# sdram_sram.net
KiCad netlist of a schematic drawn in Altium Designer
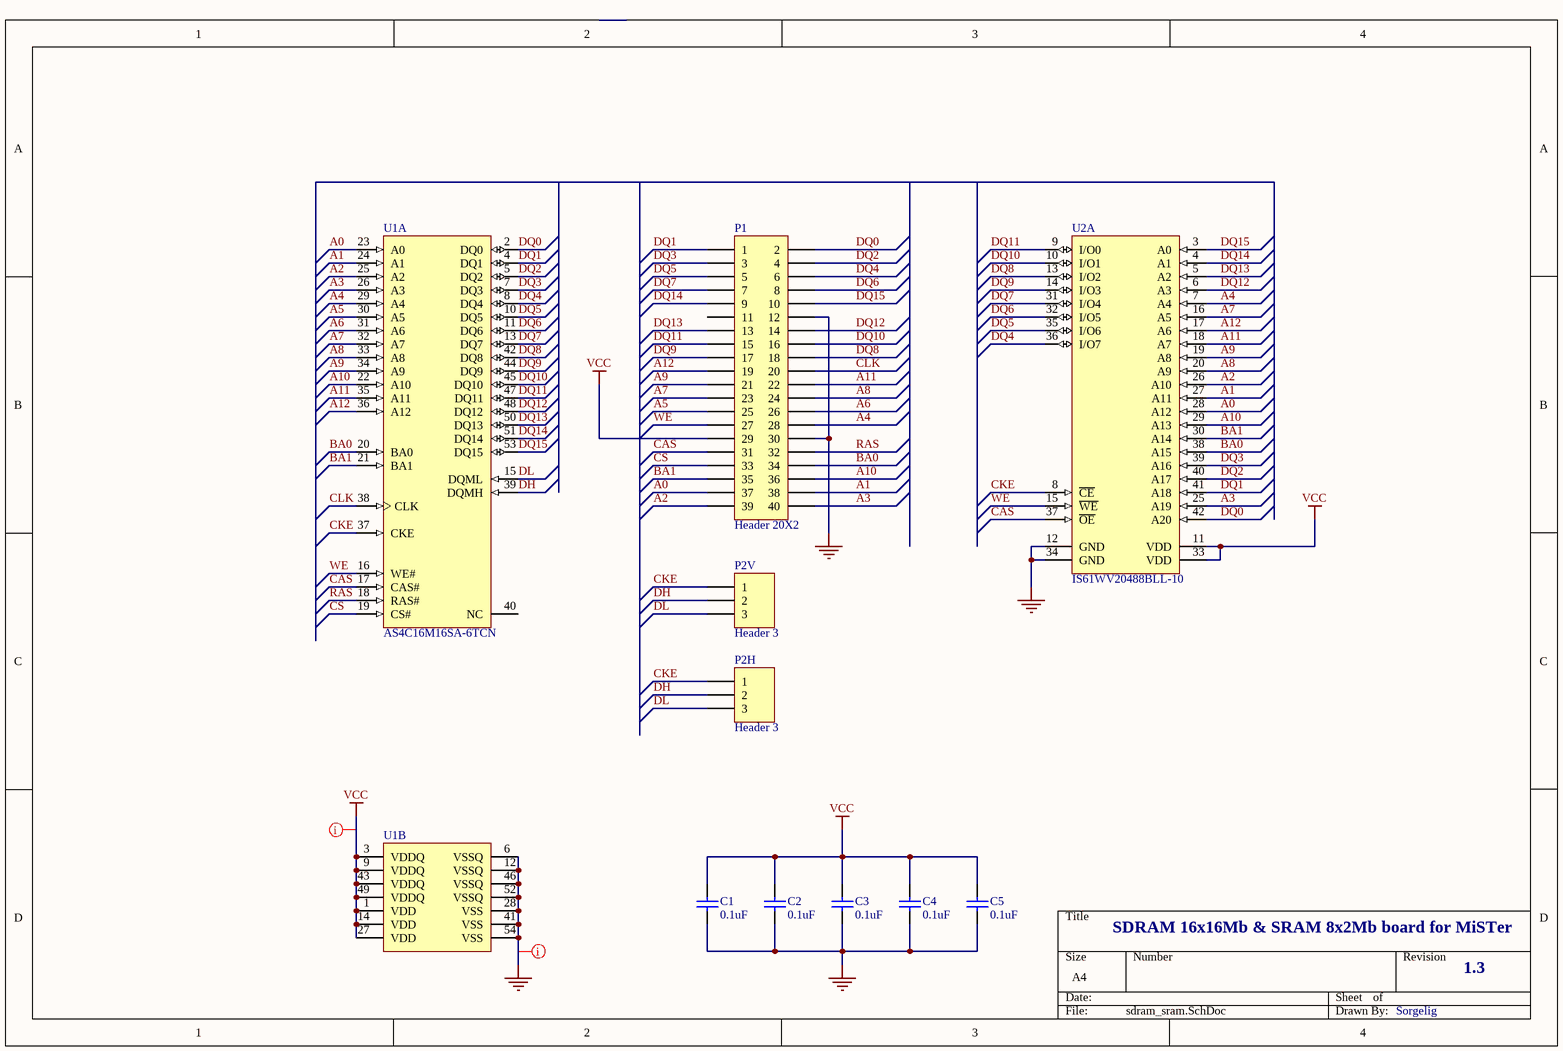
[diagram p0: sdram_sram.SchDoc]

(export (version "E")
  (design (tool "Eeschema 10.0.6"))
  (components
    (comp (ref "C1")
      (value "0.1uF")
      (footprint "C0805")
      (description "Ceramic Chip Capacitor - Standard")
      (fields (field (name "Comment") "C0805") (field (name "PUBLISHER") "Altium Limited"))
      (libsource (lib "lib") (part "C0805"))
    )
    (comp (ref "C2")
      (value "0.1uF")
      (footprint "C0805")
      (description "Ceramic Chip Capacitor - Standard")
      (fields (field (name "Comment") "C0805") (field (name "PUBLISHER") "Altium Limited"))
      (libsource (lib "lib") (part "C0805"))
    )
    (comp (ref "C3")
      (value "0.1uF")
      (footprint "C0805")
      (description "Ceramic Chip Capacitor - Standard")
      (fields (field (name "Comment") "+") (field (name "PUBLISHER") "Altium Limited"))
      (libsource (lib "lib") (part "C0805"))
    )
    (comp (ref "C4")
      (value "0.1uF")
      (footprint "C0805")
      (description "Ceramic Chip Capacitor - Standard")
      (fields (field (name "Comment") "C0805") (field (name "PUBLISHER") "Altium Limited"))
      (libsource (lib "lib") (part "C0805"))
    )
    (comp (ref "C5")
      (value "0.1uF")
      (footprint "C0805")
      (description "Ceramic Chip Capacitor - Standard")
      (fields (field (name "Comment") "+") (field (name "PUBLISHER") "Altium Limited"))
      (libsource (lib "lib") (part "C0805"))
    )
    (comp (ref "P1")
      (value "Header 20X2")
      (footprint "HDR20x2_90")
      (description "Header, 20-Pin, Dual row")
      (fields (field (name "PUBLISHER") "Altium Limited"))
      (libsource (lib "Miscellaneous Connectors") (part "Header 20X2"))
    )
    (comp (ref "P2H")
      (value "Header 3")
      (footprint "HDR1X3")
      (description "Header, 3-Pin")
      (fields (field (name "PUBLISHER") "Altium Limited"))
      (libsource (lib "Miscellaneous Connectors") (part "Header 3"))
    )
    (comp (ref "P2V")
      (value "Header 3")
      (footprint "HDR1X3")
      (description "Header, 3-Pin")
      (fields (field (name "PUBLISHER") "Altium Limited"))
      (libsource (lib "Miscellaneous Connectors") (part "Header 3"))
    )
    (comp (ref "U1")
      (value "AS4C16M16SA-6TCN")
      (footprint "TSOP54")
      (description "256Mb SDR SDRAM, 16Mb x 16, 6ns, 3.3V, 54-Pin TSOP")
      (fields (field (name "VOLTAGE") "3.3V ") (field (name "MANUFACTURER") "Micron"))
      (libsource (lib "lib") (part "AS4C16M16SA-6TCN"))
    )
    (comp (ref "U2")
      (value "IS61WV20488BLL-10")
      (footprint "ISSI-TSOP-2-44_N")
      (description "16 M High Speed CMOS SRAM, 2 M x 8, -40 to 85 degC, 44-Pin SOP (TSOP-2-44)")
      (fields
        (field (name "MANUFACTURER") "Integrated Silicon Solution Inc (ISSI)")
        (field (name "PARTNUMBER") "IS61WV20488BLL-10TI")
      )
      (libsource (lib "ISSI SRAM Asynchronous SRAM High Speed Low Power") (part "IS61WV20488BLL-10TI"))
    )
  )
  (nets
    (net (code "1") (name "/A0") (class "Default")
      (node (ref "P1") (pin "37") (pinfunction "37_37") (pintype "passive"))
      (node (ref "U1") (pin "23") (pinfunction "A0_23") (pintype "input"))
      (node (ref "U2") (pin "28") (pinfunction "A12_28") (pintype "input"))
    )
    (net (code "2") (name "/A1") (class "Default")
      (node (ref "P1") (pin "38") (pinfunction "38_38") (pintype "passive"))
      (node (ref "U1") (pin "24") (pinfunction "A1_24") (pintype "input"))
      (node (ref "U2") (pin "27") (pinfunction "A11_27") (pintype "input"))
    )
    (net (code "3") (name "/A2") (class "Default")
      (node (ref "P1") (pin "39") (pinfunction "39_39") (pintype "passive"))
      (node (ref "U1") (pin "25") (pinfunction "A2_25") (pintype "input"))
      (node (ref "U2") (pin "26") (pinfunction "A10_26") (pintype "input"))
    )
    (net (code "4") (name "/A3") (class "Default")
      (node (ref "P1") (pin "40") (pinfunction "40_40") (pintype "passive"))
      (node (ref "U1") (pin "26") (pinfunction "A3_26") (pintype "input"))
      (node (ref "U2") (pin "25") (pinfunction "A19_25") (pintype "input"))
    )
    (net (code "5") (name "/A4") (class "Default")
      (node (ref "P1") (pin "28") (pinfunction "28_28") (pintype "passive"))
      (node (ref "U1") (pin "29") (pinfunction "A4_29") (pintype "input"))
      (node (ref "U2") (pin "7") (pinfunction "A4_7") (pintype "input"))
    )
    (net (code "6") (name "/A5") (class "Default")
      (node (ref "P1") (pin "25") (pinfunction "25_25") (pintype "passive"))
      (node (ref "U1") (pin "30") (pinfunction "A5_30") (pintype "input"))
    )
    (net (code "7") (name "/A6") (class "Default")
      (node (ref "P1") (pin "26") (pinfunction "26_26") (pintype "passive"))
      (node (ref "U1") (pin "31") (pinfunction "A6_31") (pintype "input"))
    )
    (net (code "8") (name "/A7") (class "Default")
      (node (ref "P1") (pin "23") (pinfunction "23_23") (pintype "passive"))
      (node (ref "U1") (pin "32") (pinfunction "A7_32") (pintype "input"))
      (node (ref "U2") (pin "16") (pinfunction "A5_16") (pintype "input"))
    )
    (net (code "9") (name "/A8") (class "Default")
      (node (ref "P1") (pin "24") (pinfunction "24_24") (pintype "passive"))
      (node (ref "U1") (pin "33") (pinfunction "A8_33") (pintype "input"))
      (node (ref "U2") (pin "20") (pinfunction "A9_20") (pintype "input"))
    )
    (net (code "10") (name "/A9") (class "Default")
      (node (ref "P1") (pin "21") (pinfunction "21_21") (pintype "passive"))
      (node (ref "U1") (pin "34") (pinfunction "A9_34") (pintype "input"))
      (node (ref "U2") (pin "19") (pinfunction "A8_19") (pintype "input"))
    )
    (net (code "11") (name "/A10") (class "Default")
      (node (ref "P1") (pin "36") (pinfunction "36_36") (pintype "passive"))
      (node (ref "U1") (pin "22") (pinfunction "A10_22") (pintype "input"))
      (node (ref "U2") (pin "29") (pinfunction "A13_29") (pintype "input"))
    )
    (net (code "12") (name "/A11") (class "Default")
      (node (ref "P1") (pin "22") (pinfunction "22_22") (pintype "passive"))
      (node (ref "U1") (pin "35") (pinfunction "A11_35") (pintype "input"))
      (node (ref "U2") (pin "18") (pinfunction "A7_18") (pintype "input"))
    )
    (net (code "13") (name "/A12") (class "Default")
      (node (ref "P1") (pin "19") (pinfunction "19_19") (pintype "passive"))
      (node (ref "U1") (pin "36") (pinfunction "A12_36") (pintype "input"))
      (node (ref "U2") (pin "17") (pinfunction "A6_17") (pintype "input"))
    )
    (net (code "14") (name "/BA0") (class "Default")
      (node (ref "P1") (pin "34") (pinfunction "34_34") (pintype "passive"))
      (node (ref "U1") (pin "20") (pinfunction "BA0_20") (pintype "input"))
      (node (ref "U2") (pin "38") (pinfunction "A15_38") (pintype "input"))
    )
    (net (code "15") (name "/BA1") (class "Default")
      (node (ref "P1") (pin "35") (pinfunction "35_35") (pintype "passive"))
      (node (ref "U1") (pin "21") (pinfunction "BA1_21") (pintype "input"))
      (node (ref "U2") (pin "30") (pinfunction "A14_30") (pintype "input"))
    )
    (net (code "16") (name "/CAS") (class "Default")
      (node (ref "P1") (pin "31") (pinfunction "31_31") (pintype "passive"))
      (node (ref "U1") (pin "17") (pinfunction "CAS#_17") (pintype "input"))
      (node (ref "U2") (pin "37") (pinfunction "~{OE}_37") (pintype "input"))
    )
    (net (code "17") (name "/CKE") (class "Default")
      (node (ref "P2H") (pin "1") (pinfunction "1_1") (pintype "passive"))
      (node (ref "P2V") (pin "1") (pinfunction "1_1") (pintype "passive"))
      (node (ref "U1") (pin "37") (pinfunction "CKE_37") (pintype "input"))
      (node (ref "U2") (pin "8") (pinfunction "~{CE}_8") (pintype "input"))
    )
    (net (code "18") (name "/CLK") (class "Default")
      (node (ref "P1") (pin "20") (pinfunction "20_20") (pintype "passive"))
      (node (ref "U1") (pin "38") (pinfunction "CLK_38") (pintype "input"))
    )
    (net (code "19") (name "/CS") (class "Default")
      (node (ref "P1") (pin "33") (pinfunction "33_33") (pintype "passive"))
      (node (ref "U1") (pin "19") (pinfunction "CS#_19") (pintype "input"))
    )
    (net (code "20") (name "/DH") (class "Default")
      (node (ref "P2H") (pin "2") (pinfunction "2_2") (pintype "passive"))
      (node (ref "P2V") (pin "2") (pinfunction "2_2") (pintype "passive"))
      (node (ref "U1") (pin "39") (pinfunction "DQMH_39") (pintype "input"))
    )
    (net (code "21") (name "/DL") (class "Default")
      (node (ref "P2H") (pin "3") (pinfunction "3_3") (pintype "passive"))
      (node (ref "P2V") (pin "3") (pinfunction "3_3") (pintype "passive"))
      (node (ref "U1") (pin "15") (pinfunction "DQML_15") (pintype "input"))
    )
    (net (code "22") (name "/DQ0") (class "Default")
      (node (ref "P1") (pin "2") (pinfunction "2_2") (pintype "passive"))
      (node (ref "U1") (pin "2") (pinfunction "DQ0_2") (pintype "bidirectional"))
      (node (ref "U2") (pin "42") (pinfunction "A20_42") (pintype "input"))
    )
    (net (code "23") (name "/DQ1") (class "Default")
      (node (ref "P1") (pin "1") (pinfunction "1_1") (pintype "passive"))
      (node (ref "U1") (pin "4") (pinfunction "DQ1_4") (pintype "bidirectional"))
      (node (ref "U2") (pin "41") (pinfunction "A18_41") (pintype "input"))
    )
    (net (code "24") (name "/DQ2") (class "Default")
      (node (ref "P1") (pin "4") (pinfunction "4_4") (pintype "passive"))
      (node (ref "U1") (pin "5") (pinfunction "DQ2_5") (pintype "bidirectional"))
      (node (ref "U2") (pin "40") (pinfunction "A17_40") (pintype "input"))
    )
    (net (code "25") (name "/DQ3") (class "Default")
      (node (ref "P1") (pin "3") (pinfunction "3_3") (pintype "passive"))
      (node (ref "U1") (pin "7") (pinfunction "DQ3_7") (pintype "bidirectional"))
      (node (ref "U2") (pin "39") (pinfunction "A16_39") (pintype "input"))
    )
    (net (code "26") (name "/DQ4") (class "Default")
      (node (ref "P1") (pin "6") (pinfunction "6_6") (pintype "passive"))
      (node (ref "U1") (pin "8") (pinfunction "DQ4_8") (pintype "bidirectional"))
      (node (ref "U2") (pin "36") (pinfunction "I/O7_36") (pintype "bidirectional"))
    )
    (net (code "27") (name "/DQ5") (class "Default")
      (node (ref "P1") (pin "5") (pinfunction "5_5") (pintype "passive"))
      (node (ref "U1") (pin "10") (pinfunction "DQ5_10") (pintype "bidirectional"))
      (node (ref "U2") (pin "35") (pinfunction "I/O6_35") (pintype "bidirectional"))
    )
    (net (code "28") (name "/DQ6") (class "Default")
      (node (ref "P1") (pin "8") (pinfunction "8_8") (pintype "passive"))
      (node (ref "U1") (pin "11") (pinfunction "DQ6_11") (pintype "bidirectional"))
      (node (ref "U2") (pin "32") (pinfunction "I/O5_32") (pintype "bidirectional"))
    )
    (net (code "29") (name "/DQ7") (class "Default")
      (node (ref "P1") (pin "7") (pinfunction "7_7") (pintype "passive"))
      (node (ref "U1") (pin "13") (pinfunction "DQ7_13") (pintype "bidirectional"))
      (node (ref "U2") (pin "31") (pinfunction "I/O4_31") (pintype "bidirectional"))
    )
    (net (code "30") (name "/DQ8") (class "Default")
      (node (ref "P1") (pin "18") (pinfunction "18_18") (pintype "passive"))
      (node (ref "U1") (pin "42") (pinfunction "DQ8_42") (pintype "bidirectional"))
      (node (ref "U2") (pin "13") (pinfunction "I/O2_13") (pintype "bidirectional"))
    )
    (net (code "31") (name "/DQ9") (class "Default")
      (node (ref "P1") (pin "17") (pinfunction "17_17") (pintype "passive"))
      (node (ref "U1") (pin "44") (pinfunction "DQ9_44") (pintype "bidirectional"))
      (node (ref "U2") (pin "14") (pinfunction "I/O3_14") (pintype "bidirectional"))
    )
    (net (code "32") (name "/DQ10") (class "Default")
      (node (ref "P1") (pin "16") (pinfunction "16_16") (pintype "passive"))
      (node (ref "U1") (pin "45") (pinfunction "DQ10_45") (pintype "bidirectional"))
      (node (ref "U2") (pin "10") (pinfunction "I/O1_10") (pintype "bidirectional"))
    )
    (net (code "33") (name "/DQ11") (class "Default")
      (node (ref "P1") (pin "15") (pinfunction "15_15") (pintype "passive"))
      (node (ref "U1") (pin "47") (pinfunction "DQ11_47") (pintype "bidirectional"))
      (node (ref "U2") (pin "9") (pinfunction "I/O0_9") (pintype "bidirectional"))
    )
    (net (code "34") (name "/DQ12") (class "Default")
      (node (ref "P1") (pin "14") (pinfunction "14_14") (pintype "passive"))
      (node (ref "U1") (pin "48") (pinfunction "DQ12_48") (pintype "bidirectional"))
      (node (ref "U2") (pin "6") (pinfunction "A3_6") (pintype "input"))
    )
    (net (code "35") (name "/DQ13") (class "Default")
      (node (ref "P1") (pin "13") (pinfunction "13_13") (pintype "passive"))
      (node (ref "U1") (pin "50") (pinfunction "DQ13_50") (pintype "bidirectional"))
      (node (ref "U2") (pin "5") (pinfunction "A2_5") (pintype "input"))
    )
    (net (code "36") (name "/DQ14") (class "Default")
      (node (ref "P1") (pin "9") (pinfunction "9_9") (pintype "passive"))
      (node (ref "U1") (pin "51") (pinfunction "DQ14_51") (pintype "bidirectional"))
      (node (ref "U2") (pin "4") (pinfunction "A1_4") (pintype "input"))
    )
    (net (code "37") (name "/DQ15") (class "Default")
      (node (ref "P1") (pin "10") (pinfunction "10_10") (pintype "passive"))
      (node (ref "U1") (pin "53") (pinfunction "DQ15_53") (pintype "bidirectional"))
      (node (ref "U2") (pin "3") (pinfunction "A0_3") (pintype "input"))
    )
    (net (code "38") (name "/RAS") (class "Default")
      (node (ref "P1") (pin "32") (pinfunction "32_32") (pintype "passive"))
      (node (ref "U1") (pin "18") (pinfunction "RAS#_18") (pintype "input"))
    )
    (net (code "39") (name "/WE") (class "Default")
      (node (ref "P1") (pin "27") (pinfunction "27_27") (pintype "passive"))
      (node (ref "U1") (pin "16") (pinfunction "WE#_16") (pintype "input"))
      (node (ref "U2") (pin "15") (pinfunction "~{WE}_15") (pintype "input"))
    )
    (net (code "40") (name "GND") (class "Default")
      (node (ref "C1") (pin "1") (pinfunction "1_1") (pintype "passive"))
      (node (ref "C2") (pin "1") (pinfunction "1_1") (pintype "passive"))
      (node (ref "C3") (pin "1") (pinfunction "1_1") (pintype "passive"))
      (node (ref "C4") (pin "1") (pinfunction "1_1") (pintype "passive"))
      (node (ref "C5") (pin "1") (pinfunction "1_1") (pintype "passive"))
      (node (ref "P1") (pin "12") (pinfunction "12_12") (pintype "power_in"))
      (node (ref "P1") (pin "30") (pinfunction "30_30") (pintype "power_in"))
      (node (ref "U1") (pin "12") (pinfunction "VSSQ_12") (pintype "power_in"))
      (node (ref "U1") (pin "28") (pinfunction "VSS_28") (pintype "power_in"))
      (node (ref "U1") (pin "41") (pinfunction "VSS_41") (pintype "power_in"))
      (node (ref "U1") (pin "46") (pinfunction "VSSQ_46") (pintype "power_in"))
      (node (ref "U1") (pin "52") (pinfunction "VSSQ_52") (pintype "power_in"))
      (node (ref "U1") (pin "54") (pinfunction "VSS_54") (pintype "power_in"))
      (node (ref "U1") (pin "6") (pinfunction "VSSQ_6") (pintype "power_in"))
      (node (ref "U2") (pin "12") (pinfunction "GND_12") (pintype "power_in"))
      (node (ref "U2") (pin "34") (pinfunction "GND_34") (pintype "power_in"))
    )
    (net (code "41") (name "VCC") (class "Default")
      (node (ref "C1") (pin "2") (pinfunction "2_2") (pintype "passive"))
      (node (ref "C2") (pin "2") (pinfunction "2_2") (pintype "passive"))
      (node (ref "C3") (pin "2") (pinfunction "2_2") (pintype "passive"))
      (node (ref "C4") (pin "2") (pinfunction "2_2") (pintype "passive"))
      (node (ref "C5") (pin "2") (pinfunction "2_2") (pintype "passive"))
      (node (ref "P1") (pin "29") (pinfunction "29_29") (pintype "power_in"))
      (node (ref "U1") (pin "1") (pinfunction "VDD_1") (pintype "power_in"))
      (node (ref "U1") (pin "14") (pinfunction "VDD_14") (pintype "power_in"))
      (node (ref "U1") (pin "27") (pinfunction "VDD_27") (pintype "power_in"))
      (node (ref "U1") (pin "3") (pinfunction "VDDQ_3") (pintype "power_in"))
      (node (ref "U1") (pin "43") (pinfunction "VDDQ_43") (pintype "power_in"))
      (node (ref "U1") (pin "49") (pinfunction "VDDQ_49") (pintype "power_in"))
      (node (ref "U1") (pin "9") (pinfunction "VDDQ_9") (pintype "power_in"))
      (node (ref "U2") (pin "11") (pinfunction "VDD_11") (pintype "power_in"))
      (node (ref "U2") (pin "33") (pinfunction "VDD_33") (pintype "power_in"))
    )
    (net (code "42") (name "unconnected-(P1-Pad11)") (class "Default")
      (node (ref "P1") (pin "11") (pinfunction "11_11") (pintype "power_in"))
    )
    (net (code "43") (name "unconnected-(U1A-NC-Pad40)") (class "Default")
      (node (ref "U1") (pin "40") (pinfunction "NC_40") (pintype "passive"))
    )
  )
)
